# TopLevel.net
KiCad netlist of a schematic drawn in Altium Designer
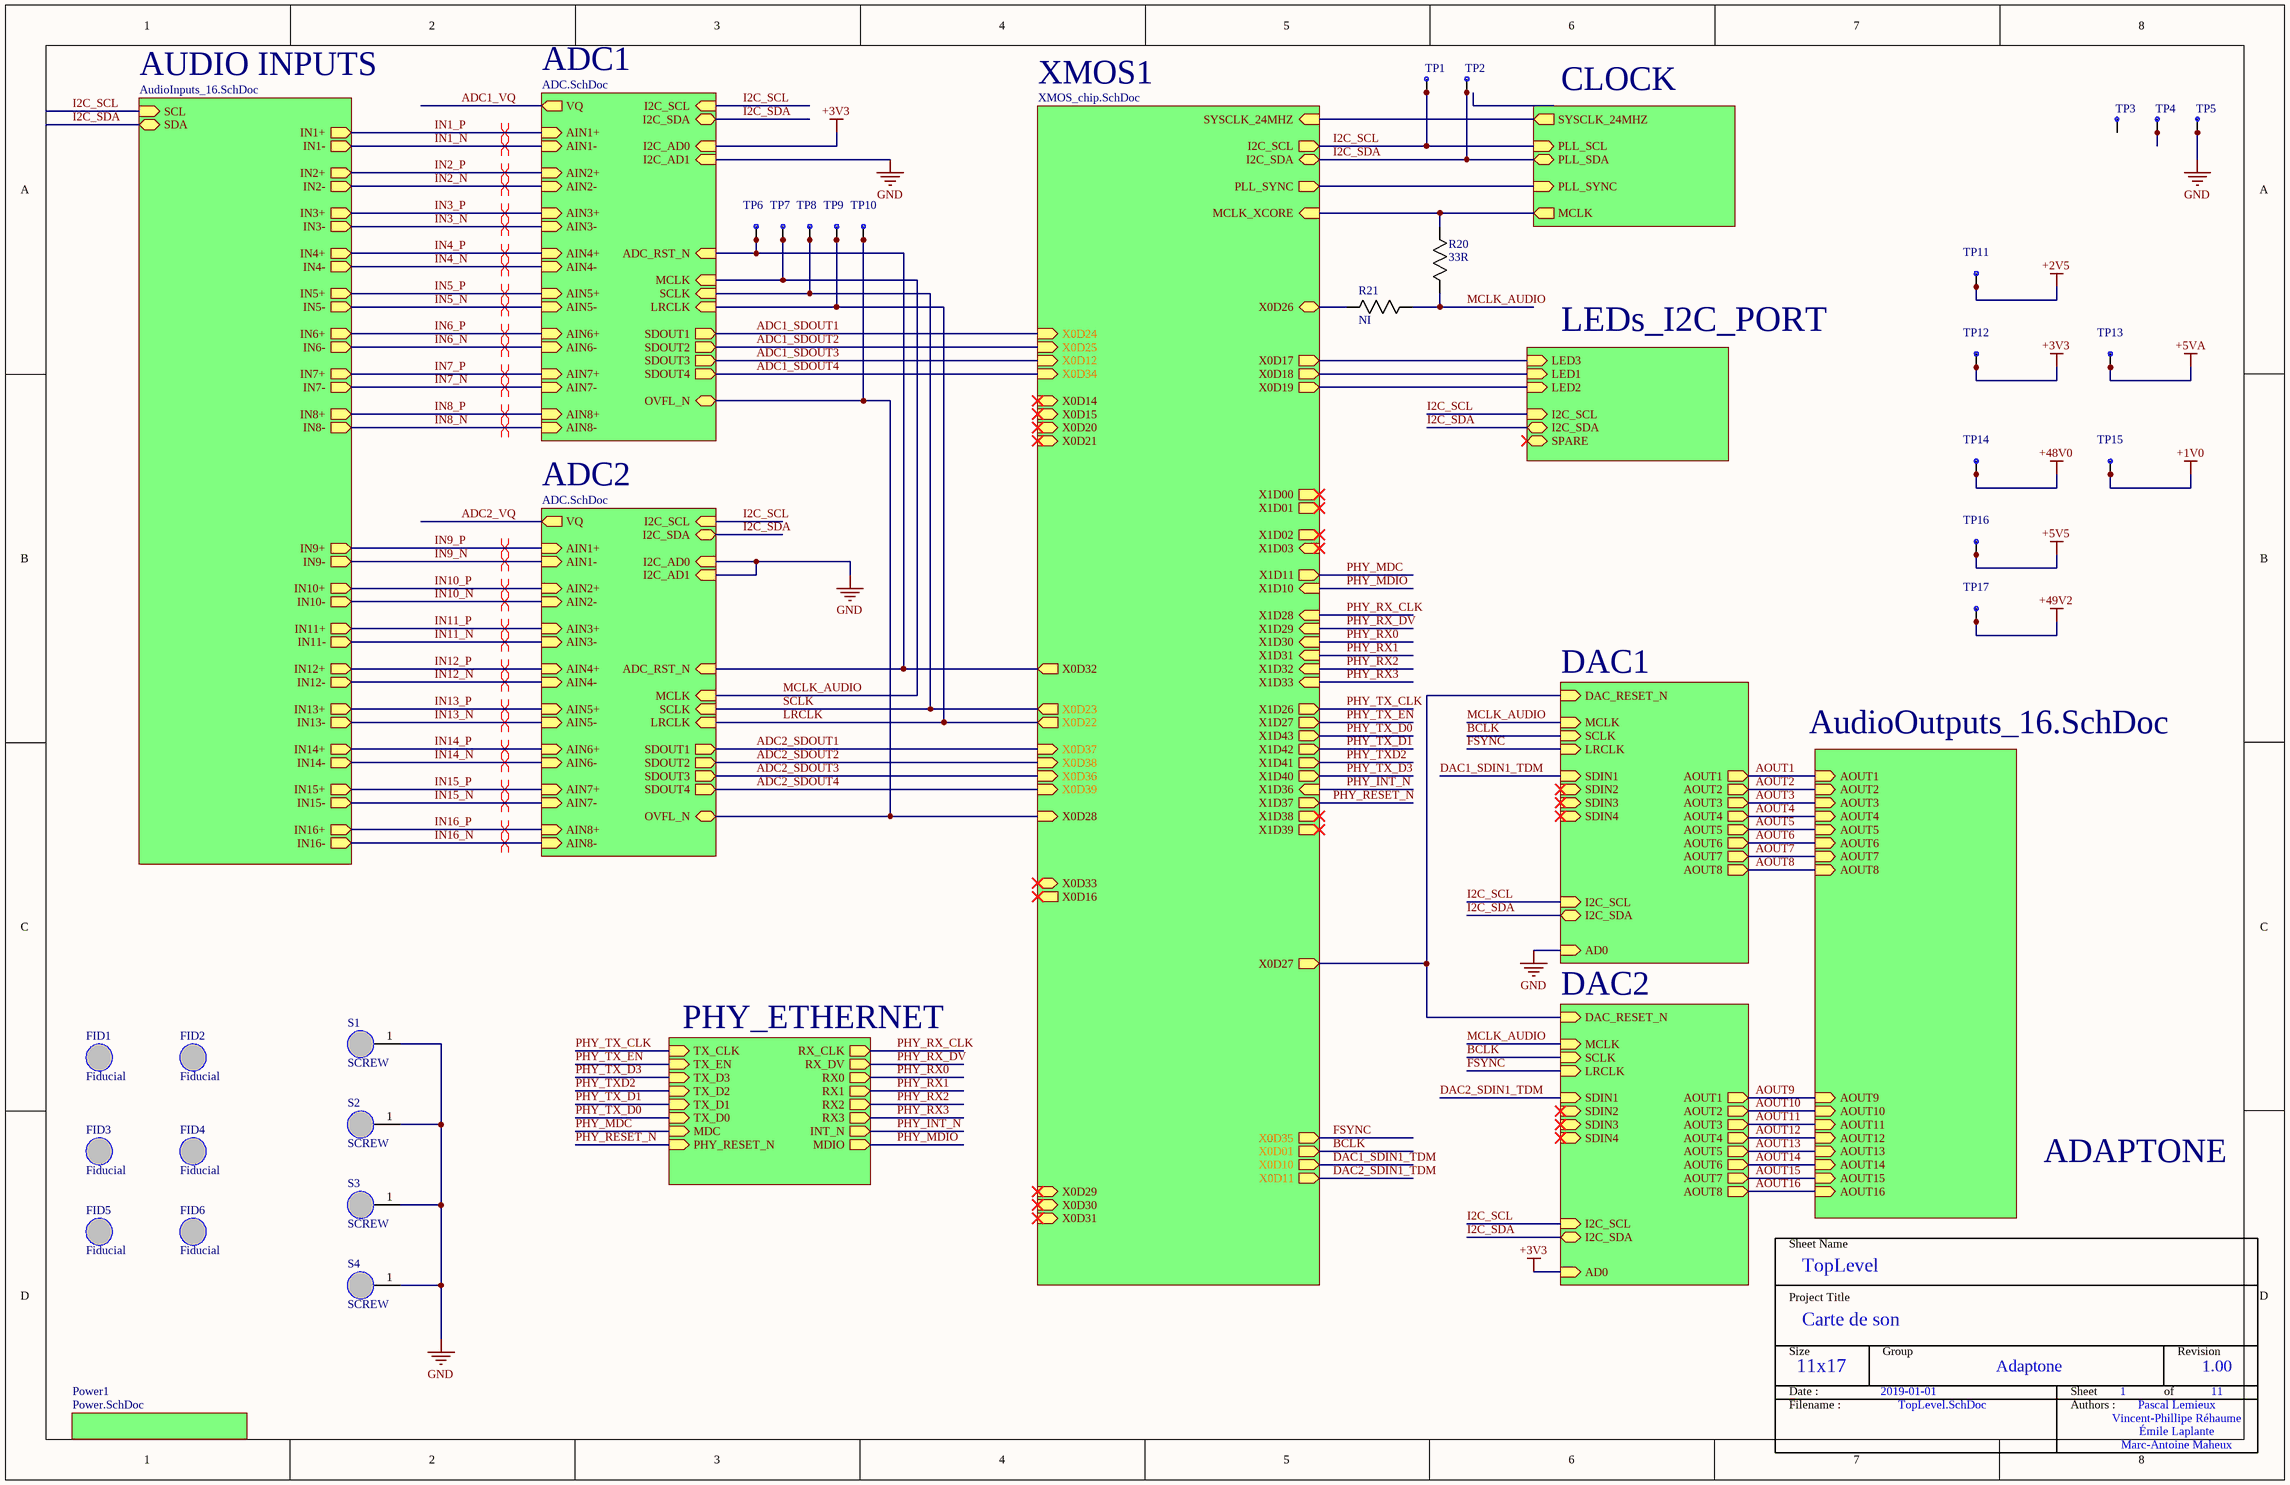
[diagram p0: TopLevel.SchDoc]

(export (version "E")
  (design (tool "Eeschema 10.0.6"))
  (components
    (comp (ref "FID1")
      (value "Fiducial")
      (footprint "FIDUCIAL")
      (libsource (lib "ADAPTONE_CARTE_DE_SON") (part "Fiducial"))
    )
    (comp (ref "FID2")
      (value "Fiducial")
      (footprint "FIDUCIAL")
      (libsource (lib "ADAPTONE_CARTE_DE_SON") (part "Fiducial"))
    )
    (comp (ref "FID3")
      (value "Fiducial")
      (footprint "FIDUCIAL")
      (libsource (lib "ADAPTONE_CARTE_DE_SON") (part "Fiducial"))
    )
    (comp (ref "FID4")
      (value "Fiducial")
      (footprint "FIDUCIAL")
      (libsource (lib "ADAPTONE_CARTE_DE_SON") (part "Fiducial"))
    )
    (comp (ref "FID5")
      (value "Fiducial")
      (footprint "FIDUCIAL")
      (libsource (lib "ADAPTONE_CARTE_DE_SON") (part "Fiducial"))
    )
    (comp (ref "FID6")
      (value "Fiducial")
      (footprint "FIDUCIAL")
      (libsource (lib "ADAPTONE_CARTE_DE_SON") (part "Fiducial"))
    )
    (comp (ref "R20")
      (value "33R")
      (footprint "0603")
      (description "Resistor")
      (fields (field (name "MFG") "Yageo"))
      (libsource (lib "ADAPTONE_CARTE_DE_SON") (part "Resistor"))
    )
    (comp (ref "R21")
      (value "Resistor")
      (footprint "0603")
      (fields (field (name "MFG") "Yageo") (field (name "NI") "NI"))
      (libsource (lib "ADAPTONE_CARTE_DE_SON") (part "Resistor"))
    )
    (comp (ref "S1")
      (value "SCREW")
      (footprint "SCREW_4_40")
      (description "Screw hole")
      (libsource (lib "ADAPTONE_CARTE_DE_SON") (part "SCREW"))
    )
    (comp (ref "S2")
      (value "SCREW")
      (footprint "SCREW_4_40")
      (description "Screw hole")
      (libsource (lib "ADAPTONE_CARTE_DE_SON") (part "SCREW"))
    )
    (comp (ref "S3")
      (value "SCREW")
      (footprint "SCREW_4_40")
      (description "Screw hole")
      (libsource (lib "ADAPTONE_CARTE_DE_SON") (part "SCREW"))
    )
    (comp (ref "S4")
      (value "SCREW")
      (footprint "SCREW_4_40")
      (description "Screw hole")
      (libsource (lib "ADAPTONE_CARTE_DE_SON") (part "SCREW"))
    )
    (comp (ref "TP1")
      (value "TESTPOINT")
      (footprint "0603")
      (description "Test point")
      (fields (field (name "MFG") "TE"))
      (libsource (lib "ADAPTONE_CARTE_DE_SON") (part "TESTPOINT"))
    )
    (comp (ref "TP2")
      (value "TESTPOINT")
      (footprint "0603")
      (description "Test point")
      (fields (field (name "MFG") "TE"))
      (libsource (lib "ADAPTONE_CARTE_DE_SON") (part "TESTPOINT"))
    )
    (comp (ref "TP3")
      (value "TESTPOINT")
      (footprint "0603")
      (description "Test point")
      (fields (field (name "MFG") "Harwin"))
      (libsource (lib "ADAPTONE_CARTE_DE_SON") (part "TESTPOINT"))
    )
    (comp (ref "TP4")
      (value "TESTPOINT")
      (footprint "0603")
      (description "Test point")
      (fields (field (name "MFG") "Harwin"))
      (libsource (lib "ADAPTONE_CARTE_DE_SON") (part "TESTPOINT"))
    )
    (comp (ref "TP5")
      (value "TESTPOINT")
      (footprint "0603")
      (description "Test point")
      (fields (field (name "MFG") "Harwin"))
      (libsource (lib "ADAPTONE_CARTE_DE_SON") (part "TESTPOINT"))
    )
    (comp (ref "TP6")
      (value "TESTPOINT")
      (footprint "0603")
      (description "Test point")
      (fields (field (name "MFG") "TE"))
      (libsource (lib "ADAPTONE_CARTE_DE_SON") (part "TESTPOINT"))
    )
    (comp (ref "TP7")
      (value "TESTPOINT")
      (footprint "0603")
      (description "Test point")
      (fields (field (name "MFG") "TE"))
      (libsource (lib "ADAPTONE_CARTE_DE_SON") (part "TESTPOINT"))
    )
    (comp (ref "TP8")
      (value "TESTPOINT")
      (footprint "0603")
      (description "Test point")
      (fields (field (name "MFG") "TE"))
      (libsource (lib "ADAPTONE_CARTE_DE_SON") (part "TESTPOINT"))
    )
    (comp (ref "TP9")
      (value "TESTPOINT")
      (footprint "0603")
      (description "Test point")
      (fields (field (name "MFG") "TE"))
      (libsource (lib "ADAPTONE_CARTE_DE_SON") (part "TESTPOINT"))
    )
    (comp (ref "TP10")
      (value "TESTPOINT")
      (footprint "0603")
      (description "Test point")
      (fields (field (name "MFG") "TE"))
      (libsource (lib "ADAPTONE_CARTE_DE_SON") (part "TESTPOINT"))
    )
    (comp (ref "TP11")
      (value "TESTPOINT")
      (footprint "0603")
      (description "Test point")
      (fields (field (name "MFG") "TE"))
      (libsource (lib "ADAPTONE_CARTE_DE_SON") (part "TESTPOINT"))
    )
    (comp (ref "TP12")
      (value "TESTPOINT")
      (footprint "0603")
      (description "Test point")
      (fields (field (name "MFG") "TE"))
      (libsource (lib "ADAPTONE_CARTE_DE_SON") (part "TESTPOINT"))
    )
    (comp (ref "TP13")
      (value "TESTPOINT")
      (footprint "0603")
      (description "Test point")
      (fields (field (name "MFG") "TE"))
      (libsource (lib "ADAPTONE_CARTE_DE_SON") (part "TESTPOINT"))
    )
    (comp (ref "TP14")
      (value "TESTPOINT")
      (footprint "0603")
      (description "Test point")
      (fields (field (name "MFG") "TE"))
      (libsource (lib "ADAPTONE_CARTE_DE_SON") (part "TESTPOINT"))
    )
    (comp (ref "TP15")
      (value "TESTPOINT")
      (footprint "0603")
      (description "Test point")
      (fields (field (name "MFG") "TE"))
      (libsource (lib "ADAPTONE_CARTE_DE_SON") (part "TESTPOINT"))
    )
    (comp (ref "TP16")
      (value "TESTPOINT")
      (footprint "0603")
      (description "Test point")
      (fields (field (name "MFG") "TE"))
      (libsource (lib "ADAPTONE_CARTE_DE_SON") (part "TESTPOINT"))
    )
    (comp (ref "TP17")
      (value "TESTPOINT")
      (footprint "0603")
      (description "Test point")
      (fields (field (name "MFG") "TE"))
      (libsource (lib "ADAPTONE_CARTE_DE_SON") (part "TESTPOINT"))
    )
  )
  (nets
    (net (code "1") (name "+1V0") (class "Default")
      (node (ref "TP15") (pin "1") (pintype "passive"))
      (node (ref "TP15") (pin "2") (pintype "passive"))
    )
    (net (code "2") (name "+2V5") (class "Default")
      (node (ref "TP11") (pin "1") (pintype "passive"))
      (node (ref "TP11") (pin "2") (pintype "passive"))
    )
    (net (code "3") (name "+3V3") (class "Default")
      (node (ref "TP12") (pin "1") (pintype "passive"))
      (node (ref "TP12") (pin "2") (pintype "passive"))
    )
    (net (code "4") (name "+5V5") (class "Default")
      (node (ref "TP16") (pin "1") (pintype "passive"))
      (node (ref "TP16") (pin "2") (pintype "passive"))
    )
    (net (code "5") (name "+5VA") (class "Default")
      (node (ref "TP13") (pin "1") (pintype "passive"))
      (node (ref "TP13") (pin "2") (pintype "passive"))
    )
    (net (code "6") (name "+48V0") (class "Default")
      (node (ref "TP14") (pin "1") (pintype "passive"))
      (node (ref "TP14") (pin "2") (pintype "passive"))
    )
    (net (code "7") (name "+49V2") (class "Default")
      (node (ref "TP17") (pin "1") (pintype "passive"))
      (node (ref "TP17") (pin "2") (pintype "passive"))
    )
    (net (code "38") (name "/I2C_SCL") (class "Default")
      (node (ref "TP1") (pin "1") (pintype "passive"))
      (node (ref "TP1") (pin "2") (pintype "passive"))
    )
    (net (code "39") (name "/I2C_SDA") (class "Default")
      (node (ref "TP2") (pin "1") (pintype "passive"))
      (node (ref "TP2") (pin "2") (pintype "passive"))
    )
    (net (code "72") (name "/LRCLK") (class "Default")
      (node (ref "TP9") (pin "1") (pintype "passive"))
      (node (ref "TP9") (pin "2") (pintype "passive"))
    )
    (net (code "73") (name "/MCLK") (class "Default") (node (ref "R20") (pin "2") (pintype "passive")))
    (net (code "74") (name "/MCLK_AUDIO") (class "Default")
      (node (ref "R20") (pin "1") (pintype "passive"))
      (node (ref "R21") (pin "2") (pintype "passive"))
      (node (ref "TP7") (pin "1") (pintype "passive"))
      (node (ref "TP7") (pin "2") (pintype "passive"))
    )
    (net (code "75") (name "/OVFL_N") (class "Default")
      (node (ref "TP10") (pin "1") (pintype "passive"))
      (node (ref "TP10") (pin "2") (pintype "passive"))
    )
    (net (code "93") (name "/SCLK") (class "Default")
      (node (ref "TP8") (pin "1") (pintype "passive"))
      (node (ref "TP8") (pin "2") (pintype "passive"))
    )
    (net (code "110") (name "/X0D26") (class "Default") (node (ref "R21") (pin "1") (pintype "passive")))
    (net (code "115") (name "/X0D32") (class "Default")
      (node (ref "TP6") (pin "1") (pintype "passive"))
      (node (ref "TP6") (pin "2") (pintype "passive"))
    )
    (net (code "123") (name "GND") (class "Default")
      (node (ref "S1") (pin "1") (pintype "passive"))
      (node (ref "S2") (pin "1") (pintype "passive"))
      (node (ref "S3") (pin "1") (pintype "passive"))
      (node (ref "S4") (pin "1") (pintype "passive"))
      (node (ref "TP5") (pin "1") (pintype "passive"))
      (node (ref "TP5") (pin "2") (pintype "passive"))
    )
    (net (code "124") (name "Net-(TP3-Pad1)") (class "Default")
      (node (ref "TP3") (pin "1") (pintype "passive"))
      (node (ref "TP3") (pin "2") (pintype "passive"))
    )
    (net (code "125") (name "Net-(TP4-Pad1)") (class "Default")
      (node (ref "TP4") (pin "1") (pintype "passive"))
      (node (ref "TP4") (pin "2") (pintype "passive"))
    )
    (net (code "126") (name "unconnected-(FID1-Pad0)") (class "Default")
      (node (ref "FID1") (pin "0") (pintype "passive"))
    )
    (net (code "127") (name "unconnected-(FID2-Pad0)") (class "Default")
      (node (ref "FID2") (pin "0") (pintype "passive"))
    )
    (net (code "128") (name "unconnected-(FID3-Pad0)") (class "Default")
      (node (ref "FID3") (pin "0") (pintype "passive"))
    )
    (net (code "129") (name "unconnected-(FID4-Pad0)") (class "Default")
      (node (ref "FID4") (pin "0") (pintype "passive"))
    )
    (net (code "130") (name "unconnected-(FID5-Pad0)") (class "Default")
      (node (ref "FID5") (pin "0") (pintype "passive"))
    )
    (net (code "131") (name "unconnected-(FID6-Pad0)") (class "Default")
      (node (ref "FID6") (pin "0") (pintype "passive"))
    )
  )
)
